# BEP31_final_stencil.net
KiCad netlist of a schematic drawn in EAGLE
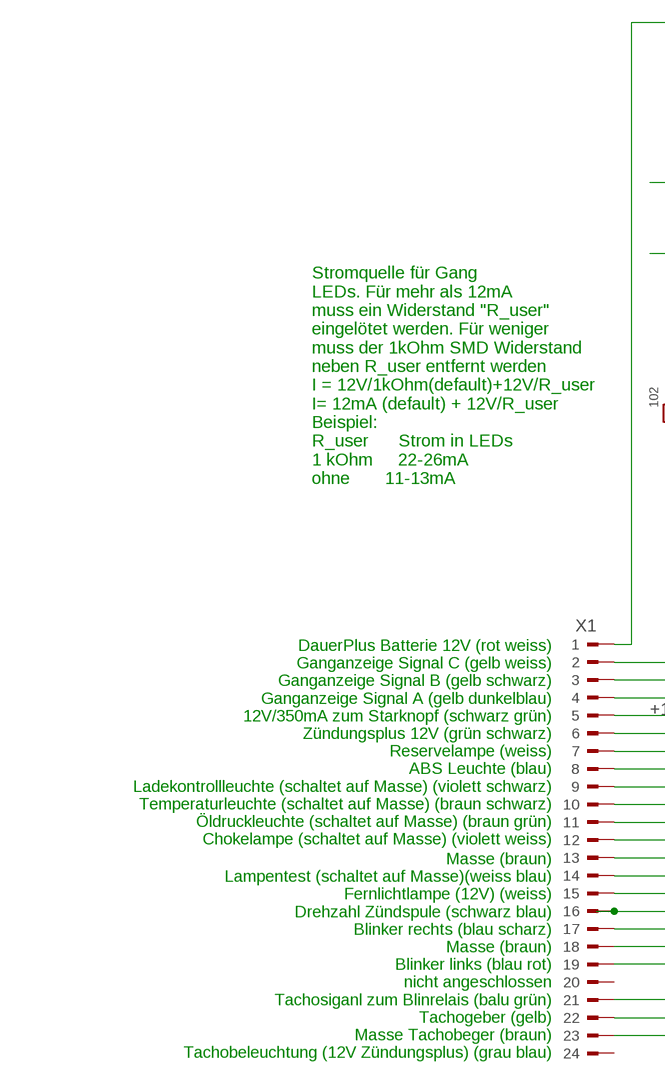
[diagram p0: schematic, sheet 1, part 1 of 2]
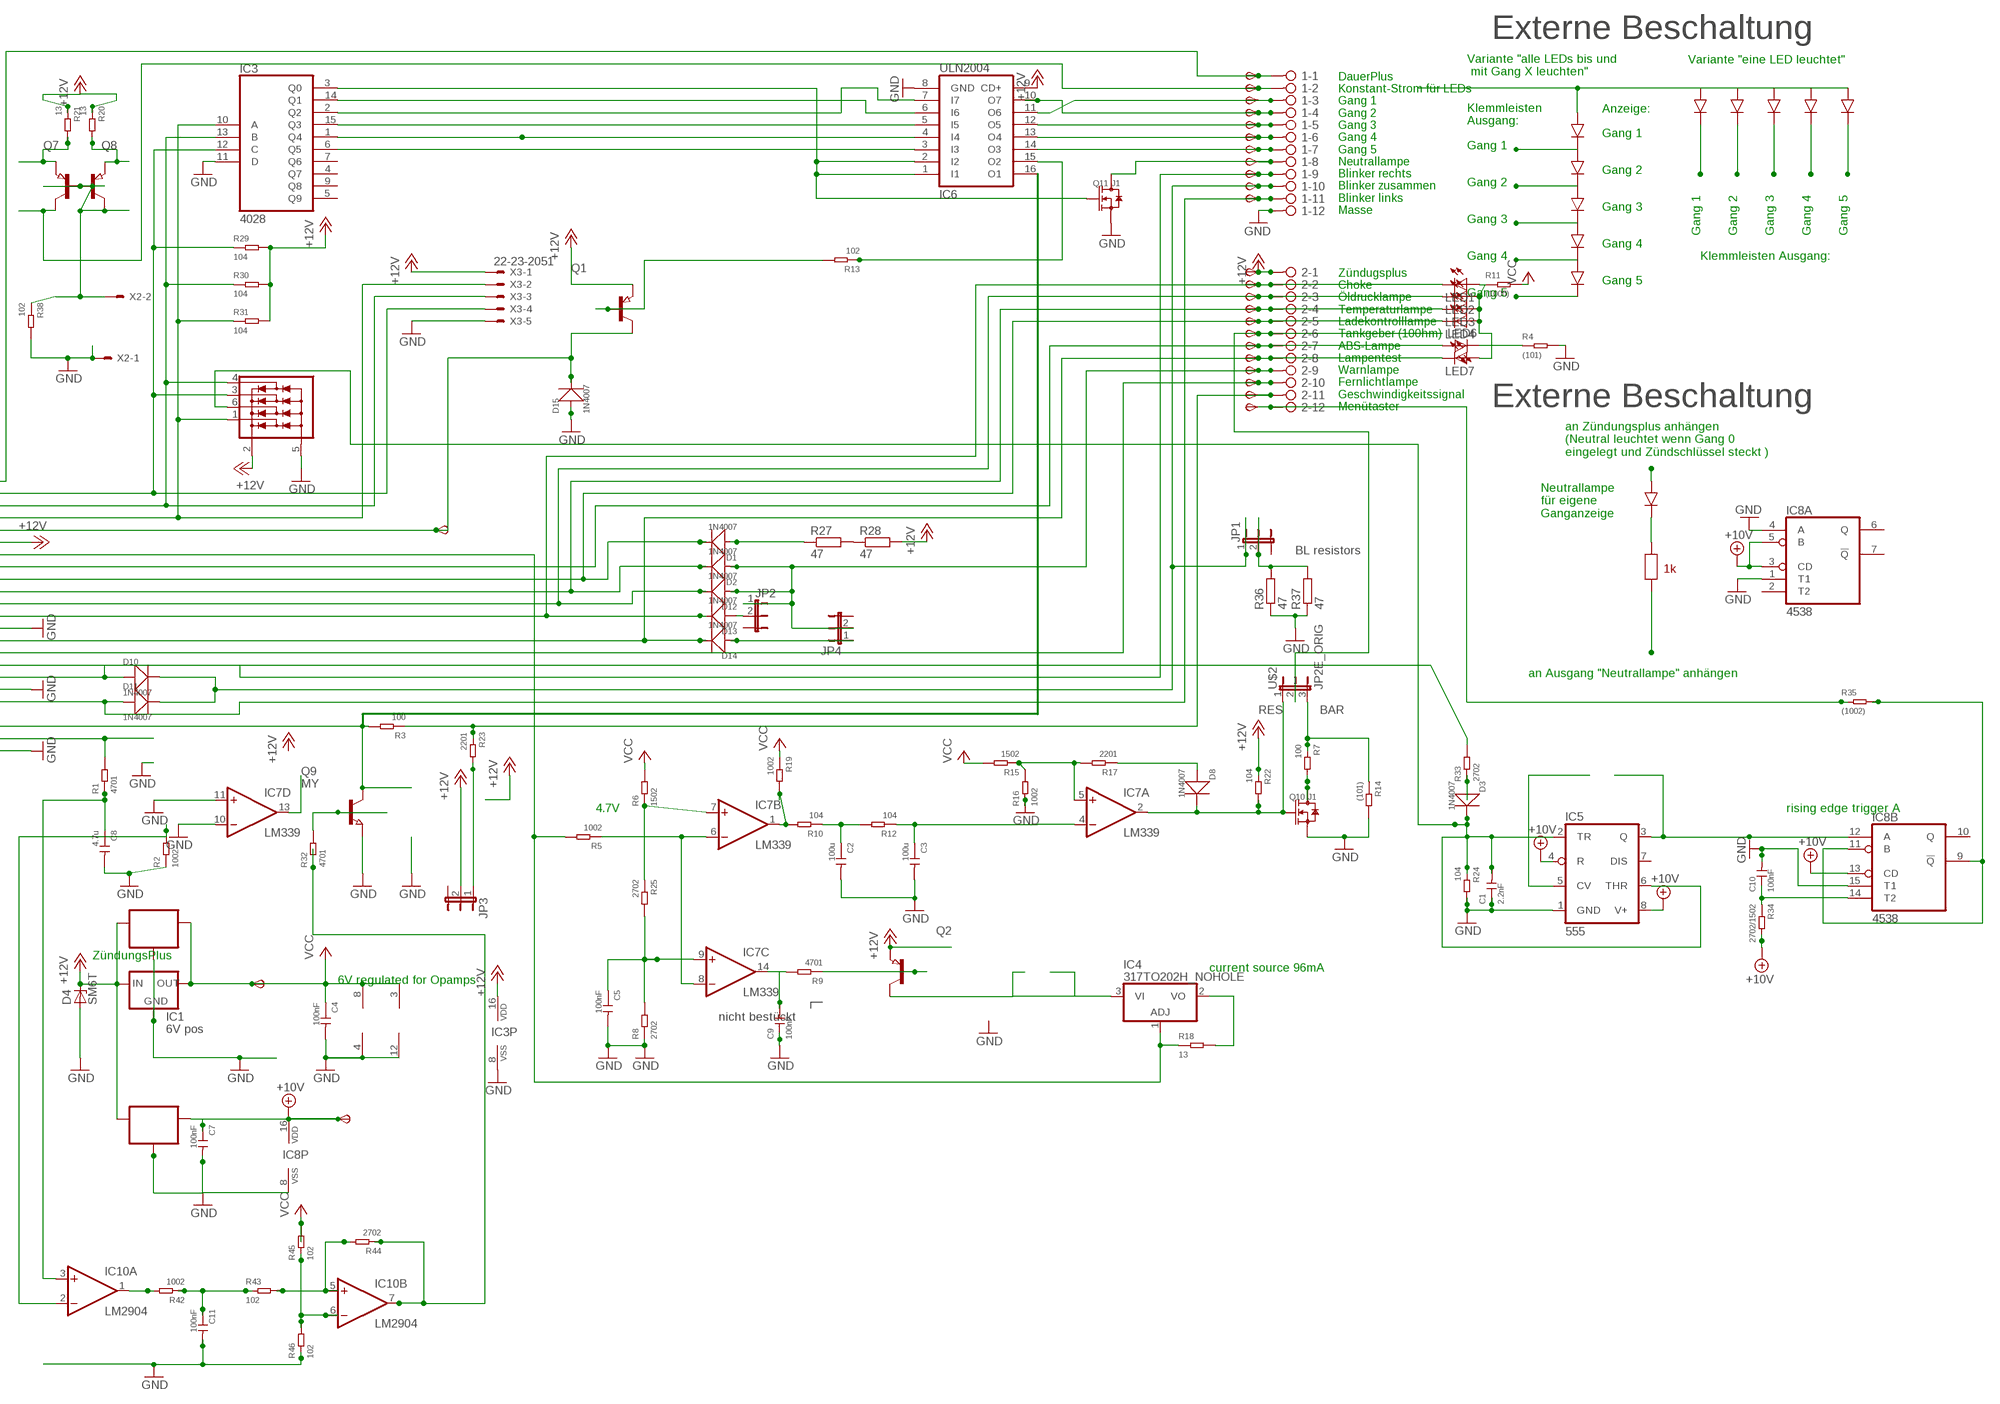
[diagram p1: schematic, sheet 1, part 2 of 2]

(export (version "E")
  (design (tool "Eeschema 10.0.6"))
  (components
    (comp (ref "1")
      (value "2081-1132")
      (footprint "eagle-import:12-PIN")
      (libsource (lib "eagle-import") (part "2081-1132"))
    )
    (comp (ref "2")
      (value "2081-1132")
      (footprint "eagle-import:12-PIN")
      (libsource (lib "eagle-import") (part "2081-1132"))
    )
    (comp (ref "6V")
      (value "TPSB2.0")
      (footprint "eagle-import:B2.0")
      (libsource (lib "eagle-import") (part "TPSB2.0"))
    )
    (comp (ref "10V")
      (value "TPSB2.0")
      (footprint "eagle-import:B2.0")
      (libsource (lib "eagle-import") (part "TPSB2.0"))
    )
    (comp (ref "C1")
      (value "2.2nF")
      (footprint "eagle-import:C0805")
      (fields (field (name "MPN") "CC0805KRX7R9BB104"))
      (libsource (lib "eagle-import") (part "CERAMIC-100NF-50V-10%-X7R(0805)"))
    )
    (comp (ref "C2")
      (value "100u")
      (footprint "eagle-import:C1206")
      (fields (field (name "MPN") "GRM31CR60J107ME39L"))
      (libsource (lib "eagle-import") (part "CERAMIC-100UF-6.3V-20%-X5R(1206)"))
    )
    (comp (ref "C3")
      (value "100u")
      (footprint "eagle-import:C1206")
      (fields (field (name "MPN") "GRM31CR60J107ME39L"))
      (libsource (lib "eagle-import") (part "CERAMIC-100UF-6.3V-20%-X5R(1206)"))
    )
    (comp (ref "C4")
      (value "100nF")
      (footprint "eagle-import:C0805")
      (fields (field (name "MPN") "CC0805KRX7R9BB104"))
      (libsource (lib "eagle-import") (part "CERAMIC-100NF-50V-10%-X7R(0805)"))
    )
    (comp (ref "C5")
      (value "100nF")
      (footprint "eagle-import:C0805")
      (fields (field (name "MPN") "CC0805KRX7R9BB104"))
      (libsource (lib "eagle-import") (part "CERAMIC-100NF-50V-10%-X7R(0805)"))
    )
    (comp (ref "C7")
      (value "100nF")
      (footprint "eagle-import:C0805")
      (fields (field (name "MPN") "CC0805KRX7R9BB104"))
      (libsource (lib "eagle-import") (part "CERAMIC-100NF-50V-10%-X7R(0805)"))
    )
    (comp (ref "C8")
      (value "4.7u")
      (footprint "eagle-import:C0805")
      (fields (field (name "MPN") "CC0805KKX5R8BB475"))
      (libsource (lib "eagle-import") (part "CERAMIC-4.7UF-25V-10%-X5R(0805)"))
    )
    (comp (ref "C9")
      (value "100nF")
      (footprint "eagle-import:C0805")
      (fields (field (name "MPN") "CC0805KRX7R9BB104"))
      (libsource (lib "eagle-import") (part "CERAMIC-100NF-50V-10%-X7R(0805)"))
    )
    (comp (ref "C10")
      (value "100nF")
      (footprint "eagle-import:C0805")
      (fields (field (name "MPN") "CC0805KRX7R9BB104"))
      (libsource (lib "eagle-import") (part "CERAMIC-100NF-50V-10%-X7R(0805)"))
    )
    (comp (ref "C11")
      (value "100nF")
      (footprint "eagle-import:C0805")
      (fields (field (name "MPN") "CC0805KRX7R9BB104"))
      (libsource (lib "eagle-import") (part "CERAMIC-100NF-50V-10%-X7R(0805)"))
    )
    (comp (ref "D1")
      (value "1N4007")
      (footprint "eagle-import:DO-214AC")
      (libsource (lib "eagle-import") (part "DIODE-GEN-PURPOSE-1KV-1A(DO-214AC)"))
    )
    (comp (ref "D2")
      (value "1N4007")
      (footprint "eagle-import:DO-214AC-1206MOUNT")
      (libsource (lib "eagle-import") (part "DIODE-GEN-PURPOSE-1KV-1A(DO-214AC)DO-214AC/1206"))
    )
    (comp (ref "D3")
      (value "1N4007")
      (footprint "eagle-import:DO-214AC")
      (libsource (lib "eagle-import") (part "DIODE-GEN-PURPOSE-1KV-1A(DO-214AC)"))
    )
    (comp (ref "D4")
      (value "SM6T")
      (footprint "eagle-import:DO214AA")
      (libsource (lib "eagle-import") (part "SM6T"))
    )
    (comp (ref "D8")
      (value "1N4007")
      (footprint "eagle-import:DO-214AC")
      (libsource (lib "eagle-import") (part "DIODE-GEN-PURPOSE-1KV-1A(DO-214AC)"))
    )
    (comp (ref "D10")
      (value "1N4007")
      (footprint "eagle-import:DO-214AC")
      (libsource (lib "eagle-import") (part "DIODE-GEN-PURPOSE-1KV-1A(DO-214AC)"))
    )
    (comp (ref "D11")
      (value "1N4007")
      (footprint "eagle-import:DO-214AC")
      (libsource (lib "eagle-import") (part "DIODE-GEN-PURPOSE-1KV-1A(DO-214AC)"))
    )
    (comp (ref "D12")
      (value "1N4007")
      (footprint "eagle-import:DO-214AC-1206MOUNT")
      (libsource (lib "eagle-import") (part "DIODE-GEN-PURPOSE-1KV-1A(DO-214AC)DO-214AC/1206"))
    )
    (comp (ref "D13")
      (value "1N4007")
      (footprint "eagle-import:DO-214AC-1206MOUNT")
      (libsource (lib "eagle-import") (part "DIODE-GEN-PURPOSE-1KV-1A(DO-214AC)DO-214AC/1206"))
    )
    (comp (ref "D14")
      (value "1N4007")
      (footprint "eagle-import:DO-214AC-1206MOUNT")
      (libsource (lib "eagle-import") (part "DIODE-GEN-PURPOSE-1KV-1A(DO-214AC)DO-214AC/1206"))
    )
    (comp (ref "D15")
      (value "1N4007")
      (footprint "eagle-import:DO-214AC")
      (libsource (lib "eagle-import") (part "DIODE-GEN-PURPOSE-1KV-1A(DO-214AC)"))
    )
    (comp (ref "IC1")
      (value "6V pos")
      (footprint "eagle-import:78LXX")
      (libsource (lib "eagle-import") (part "v-reg_78LXX"))
    )
    (comp (ref "IC2")
      (value "78LXXSOT89_ROUND")
      (footprint "eagle-import:SOT89_ROUND")
      (libsource (lib "eagle-import") (part "78LXXSOT89_ROUND"))
    )
    (comp (ref "IC3")
      (value "4028")
      (footprint "eagle-import:SO16")
      (libsource (lib "eagle-import") (part "4028D"))
    )
    (comp (ref "IC4")
      (value "317TO202H_NOHOLE")
      (footprint "eagle-import:TO220H_NOHOLE")
      (libsource (lib "eagle-import") (part "317TO202H_NOHOLE"))
    )
    (comp (ref "IC5")
      (value "555")
      (footprint "eagle-import:SO08")
      (libsource (lib "eagle-import") (part "555DNE"))
    )
    (comp (ref "IC6")
      (value "ULN2004")
      (footprint "eagle-import:SO16")
      (libsource (lib "eagle-import") (part "ULN2004AD"))
    )
    (comp (ref "IC7")
      (value "LM339")
      (footprint "eagle-import:SO14")
      (libsource (lib "eagle-import") (part "LM339D"))
    )
    (comp (ref "IC8")
      (value "4538")
      (footprint "eagle-import:SO16")
      (libsource (lib "eagle-import") (part "4538D"))
    )
    (comp (ref "IC9")
      (value "78LXXSOT89_ROUND")
      (footprint "eagle-import:SOT89_ROUND")
      (libsource (lib "eagle-import") (part "78LXXSOT89_ROUND"))
    )
    (comp (ref "IC10")
      (value "LM2904")
      (footprint "eagle-import:SO08")
      (libsource (lib "eagle-import") (part "LM358D"))
    )
    (comp (ref "JP1")
      (value "JP2EJP2_SMALLPADS")
      (footprint "eagle-import:JP2_SMALLPADS")
      (libsource (lib "eagle-import") (part "JP2EJP2_SMALLPADS"))
    )
    (comp (ref "JP2")
      (value "JP2EJP2_SMALLPADS")
      (footprint "eagle-import:JP2_SMALLPADS")
      (libsource (lib "eagle-import") (part "JP2EJP2_SMALLPADS"))
    )
    (comp (ref "JP3")
      (value "JP2EJP2_SMALLPADS")
      (footprint "eagle-import:JP2_SMALLPADS")
      (libsource (lib "eagle-import") (part "JP2EJP2_SMALLPADS"))
    )
    (comp (ref "JP4")
      (value "JP2EJP2_SMALLPADS")
      (footprint "eagle-import:JP2_SMALLPADS")
      (libsource (lib "eagle-import") (part "JP2EJP2_SMALLPADS"))
    )
    (comp (ref "LED1")
      (value "LEDLD260")
      (footprint "eagle-import:LD260")
      (libsource (lib "eagle-import") (part "LEDLD260"))
    )
    (comp (ref "LED2")
      (value "LEDLD260")
      (footprint "eagle-import:LD260")
      (libsource (lib "eagle-import") (part "LEDLD260"))
    )
    (comp (ref "LED3")
      (value "LEDLD260")
      (footprint "eagle-import:LD260")
      (libsource (lib "eagle-import") (part "LEDLD260"))
    )
    (comp (ref "LED4")
      (value "LEDLD260")
      (footprint "eagle-import:LD260")
      (libsource (lib "eagle-import") (part "LEDLD260"))
    )
    (comp (ref "LED6")
      (value "LEDLD260")
      (footprint "eagle-import:LD260")
      (libsource (lib "eagle-import") (part "LEDLD260"))
    )
    (comp (ref "LED7")
      (value "LEDLD260")
      (footprint "eagle-import:LD260")
      (libsource (lib "eagle-import") (part "LEDLD260"))
    )
    (comp (ref "Q1")
      (value "PNP-TRANSISTOR_SOT89")
      (footprint "eagle-import:SOT89")
      (libsource (lib "eagle-import") (part "PNP-TRANSISTOR_SOT89"))
    )
    (comp (ref "Q2")
      (value "PNP-TRANSISTOR_SOT89")
      (footprint "eagle-import:SOT89")
      (libsource (lib "eagle-import") (part "PNP-TRANSISTOR_SOT89"))
    )
    (comp (ref "Q7")
      (value "PNP-TRANSISTOR_SOT89")
      (footprint "eagle-import:SOT89")
      (libsource (lib "eagle-import") (part "PNP-TRANSISTOR_SOT89"))
    )
    (comp (ref "Q8")
      (value "PNP-TRANSISTOR_SOT89")
      (footprint "eagle-import:SOT89")
      (libsource (lib "eagle-import") (part "PNP-TRANSISTOR_SOT89"))
    )
    (comp (ref "Q9")
      (value "MY")
      (footprint "eagle-import:SOT89")
      (libsource (lib "eagle-import") (part "NPN-TRANSISTOR_SOT89"))
    )
    (comp (ref "Q10")
      (value "J1")
      (footprint "eagle-import:SOT-23")
      (fields (field (name "MPN") "BSS138W-7-F"))
      (libsource (lib "eagle-import") (part "SMD-MOSFET-N-CH-50V-200MA-BSS138W-7-F(SOT-23)"))
    )
    (comp (ref "Q11")
      (value "J1")
      (footprint "eagle-import:SOT-23")
      (fields (field (name "MPN") "BSS138W-7-F"))
      (libsource (lib "eagle-import") (part "SMD-MOSFET-N-CH-50V-200MA-BSS138W-7-F(SOT-23)"))
    )
    (comp (ref "R1")
      (value "4701")
      (footprint "eagle-import:R0805")
      (fields (field (name "MPN") "RC0805JR-074K7L"))
      (libsource (lib "eagle-import") (part "SMD-RES-4.7K-5%-1/8W(0805)"))
    )
    (comp (ref "R2")
      (value "1002")
      (footprint "eagle-import:R0805")
      (fields (field (name "MPN") "RC0805FR-0710KL"))
      (libsource (lib "eagle-import") (part "SMD-RES-10K-1%-1/8W(0805)"))
    )
    (comp (ref "R3")
      (value "100")
      (footprint "eagle-import:R0805")
      (fields (field (name "MPN") "RC0805JR-07220RL"))
      (libsource (lib "eagle-import") (part "SMD-RES-220R-5%-1/8W(0805)"))
    )
    (comp (ref "R4")
      (value "(101)")
      (footprint "eagle-import:R0805")
      (fields (field (name "MPN") "RC0805JR-07100RL"))
      (libsource (lib "eagle-import") (part "SMD-RES-100R-5%-1/8W(0805)"))
    )
    (comp (ref "R5")
      (value "1002")
      (footprint "eagle-import:R0805")
      (fields (field (name "MPN") "RC0805FR-0710KL"))
      (libsource (lib "eagle-import") (part "SMD-RES-10K-1%-1/8W(0805)"))
    )
    (comp (ref "R6")
      (value "1502")
      (footprint "eagle-import:R0805")
      (fields (field (name "MPN") "RC0805FR-0710KL"))
      (libsource (lib "eagle-import") (part "SMD-RES-10K-1%-1/8W(0805)"))
    )
    (comp (ref "R7")
      (value "100")
      (footprint "eagle-import:R0805")
      (fields (field (name "MPN") "RC0805JR-072K2L"))
      (libsource (lib "eagle-import") (part "SMD-RES-2.2K-5%-1/8W(0805)"))
    )
    (comp (ref "R8")
      (value "2702")
      (footprint "eagle-import:R0805")
      (fields (field (name "MPN") "RC0805JR-074K7L"))
      (libsource (lib "eagle-import") (part "SMD-RES-4.7K-5%-1/8W(0805)"))
    )
    (comp (ref "R9")
      (value "4701")
      (footprint "eagle-import:R0805")
      (fields (field (name "MPN") "RC0805JR-074K7L"))
      (libsource (lib "eagle-import") (part "SMD-RES-4.7K-5%-1/8W(0805)"))
    )
    (comp (ref "R10")
      (value "104")
      (footprint "eagle-import:R0805")
      (fields (field (name "MPN") "RC0805FR-0710KL"))
      (libsource (lib "eagle-import") (part "SMD-RES-10K-1%-1/8W(0805)"))
    )
    (comp (ref "R11")
      (value "(1000)")
      (footprint "eagle-import:R0805")
      (fields (field (name "MPN") "RC0805JR-07100RL"))
      (libsource (lib "eagle-import") (part "SMD-RES-100R-5%-1/8W(0805)"))
    )
    (comp (ref "R12")
      (value "104")
      (footprint "eagle-import:R0805")
      (fields (field (name "MPN") "RC0805FR-0710KL"))
      (libsource (lib "eagle-import") (part "SMD-RES-10K-1%-1/8W(0805)"))
    )
    (comp (ref "R13")
      (value "102")
      (footprint "eagle-import:R0805")
      (fields (field (name "MPN") "RC0805JR-071KL"))
      (libsource (lib "eagle-import") (part "SMD-RES-1K-5%-1/8W(0805)"))
    )
    (comp (ref "R14")
      (value "(101)")
      (footprint "eagle-import:R0805")
      (fields (field (name "MPN") "RC0805JR-072K2L"))
      (libsource (lib "eagle-import") (part "SMD-RES-2.2K-5%-1/8W(0805)"))
    )
    (comp (ref "R15")
      (value "1502")
      (footprint "eagle-import:R0805")
      (fields (field (name "MPN") "RC0805FR-0710KL"))
      (libsource (lib "eagle-import") (part "SMD-RES-10K-1%-1/8W(0805)"))
    )
    (comp (ref "R16")
      (value "1002")
      (footprint "eagle-import:R0805")
      (fields (field (name "MPN") "RC0805FR-0710KL"))
      (libsource (lib "eagle-import") (part "SMD-RES-10K-1%-1/8W(0805)"))
    )
    (comp (ref "R17")
      (value "2201")
      (footprint "eagle-import:R0805")
      (fields (field (name "MPN") "RC0805JR-072K2L"))
      (libsource (lib "eagle-import") (part "SMD-RES-2.2K-5%-1/8W(0805)"))
    )
    (comp (ref "R18")
      (value "13")
      (footprint "eagle-import:R1206")
      (fields (field (name "MPN") "RC1206JR-0713RL"))
      (libsource (lib "eagle-import") (part "SMD-RES-13R-5%-1/4W(1206)"))
    )
    (comp (ref "R19")
      (value "1002")
      (footprint "eagle-import:R0805")
      (fields (field (name "MPN") "RC0805FR-0710KL"))
      (libsource (lib "eagle-import") (part "SMD-RES-10K-1%-1/8W(0805)"))
    )
    (comp (ref "R20")
      (value "13")
      (footprint "eagle-import:R1206")
      (fields (field (name "MPN") "RC1206JR-0713RL"))
      (libsource (lib "eagle-import") (part "SMD-RES-13R-5%-1/4W(1206)"))
    )
    (comp (ref "R21")
      (value "13")
      (footprint "eagle-import:R1206")
      (fields (field (name "MPN") "RC1206JR-0713RL"))
      (libsource (lib "eagle-import") (part "SMD-RES-13R-5%-1/4W(1206)"))
    )
    (comp (ref "R22")
      (value "104")
      (footprint "eagle-import:R0805")
      (fields (field (name "MPN") "RC0805FR-0710KL"))
      (libsource (lib "eagle-import") (part "SMD-RES-10K-1%-1/8W(0805)"))
    )
    (comp (ref "R23")
      (value "2201")
      (footprint "eagle-import:R0805")
      (fields (field (name "MPN") "RC0805JR-072K2L"))
      (libsource (lib "eagle-import") (part "SMD-RES-2.2K-5%-1/8W(0805)"))
    )
    (comp (ref "R24")
      (value "104")
      (footprint "eagle-import:R0805")
      (fields (field (name "MPN") "RC0805FR-0710KL"))
      (libsource (lib "eagle-import") (part "SMD-RES-10K-1%-1/8W(0805)"))
    )
    (comp (ref "R25")
      (value "2702")
      (footprint "eagle-import:R0805")
      (fields (field (name "MPN") "RC0805JR-074K7L"))
      (libsource (lib "eagle-import") (part "SMD-RES-4.7K-5%-1/8W(0805)"))
    )
    (comp (ref "R27")
      (value "47")
      (footprint "eagle-import:V235_17_1MM")
      (libsource (lib "eagle-import") (part "R-EU_V235/17_1MM"))
    )
    (comp (ref "R28")
      (value "47")
      (footprint "eagle-import:V235_17_1MM")
      (libsource (lib "eagle-import") (part "R-EU_V235/17_1MM"))
    )
    (comp (ref "R29")
      (value "104")
      (footprint "eagle-import:R0805")
      (fields (field (name "MPN") "RC0805FR-0710KL"))
      (libsource (lib "eagle-import") (part "SMD-RES-10K-1%-1/8W(0805)"))
    )
    (comp (ref "R30")
      (value "104")
      (footprint "eagle-import:R0805")
      (fields (field (name "MPN") "RC0805FR-0710KL"))
      (libsource (lib "eagle-import") (part "SMD-RES-10K-1%-1/8W(0805)"))
    )
    (comp (ref "R31")
      (value "104")
      (footprint "eagle-import:R0805")
      (fields (field (name "MPN") "RC0805FR-0710KL"))
      (libsource (lib "eagle-import") (part "SMD-RES-10K-1%-1/8W(0805)"))
    )
    (comp (ref "R32")
      (value "4701")
      (footprint "eagle-import:R0805")
      (fields (field (name "MPN") "RC0805JR-074K7L"))
      (libsource (lib "eagle-import") (part "SMD-RES-4.7K-5%-1/8W(0805)"))
    )
    (comp (ref "R33")
      (value "2702")
      (footprint "eagle-import:R0805")
      (fields (field (name "MPN") "RC0805FR-0710KL"))
      (libsource (lib "eagle-import") (part "SMD-RES-10K-1%-1/8W(0805)"))
    )
    (comp (ref "R34")
      (value "2702/1502")
      (footprint "eagle-import:R0805")
      (fields (field (name "MPN") "RC0805JR-074K7L"))
      (libsource (lib "eagle-import") (part "SMD-RES-4.7K-5%-1/8W(0805)"))
    )
    (comp (ref "R35")
      (value "(1002)")
      (footprint "eagle-import:R0805")
      (fields (field (name "MPN") "RC0805JR-074K7L"))
      (libsource (lib "eagle-import") (part "SMD-RES-4.7K-5%-1/8W(0805)"))
    )
    (comp (ref "R36")
      (value "47")
      (footprint "eagle-import:V235_17_1MM")
      (libsource (lib "eagle-import") (part "R-EU_V235/17_1MM"))
    )
    (comp (ref "R37")
      (value "47")
      (footprint "eagle-import:V235_17_1MM")
      (libsource (lib "eagle-import") (part "R-EU_V235/17_1MM"))
    )
    (comp (ref "R38")
      (value "102")
      (footprint "eagle-import:R0805")
      (fields (field (name "MPN") "RC0805JR-071KL"))
      (libsource (lib "eagle-import") (part "SMD-RES-1K-5%-1/8W(0805)"))
    )
    (comp (ref "R42")
      (value "1002")
      (footprint "eagle-import:R0805")
      (fields (field (name "MPN") "RC0805FR-0710KL"))
      (libsource (lib "eagle-import") (part "SMD-RES-10K-1%-1/8W(0805)"))
    )
    (comp (ref "R43")
      (value "102")
      (footprint "eagle-import:R0805")
      (fields (field (name "MPN") "RC0805JR-071KL"))
      (libsource (lib "eagle-import") (part "SMD-RES-1K-5%-1/8W(0805)"))
    )
    (comp (ref "R44")
      (value "2702")
      (footprint "eagle-import:R0805")
      (fields (field (name "MPN") "RC0805JR-074K7L"))
      (libsource (lib "eagle-import") (part "SMD-RES-4.7K-5%-1/8W(0805)"))
    )
    (comp (ref "R45")
      (value "102")
      (footprint "eagle-import:R0805")
      (fields (field (name "MPN") "RC0805JR-071KL"))
      (libsource (lib "eagle-import") (part "SMD-RES-1K-5%-1/8W(0805)"))
    )
    (comp (ref "R46")
      (value "102")
      (footprint "eagle-import:R0805")
      (fields (field (name "MPN") "RC0805JR-071KL"))
      (libsource (lib "eagle-import") (part "SMD-RES-1K-5%-1/8W(0805)"))
    )
    (comp (ref "START")
      (value "TPSB2.0")
      (footprint "eagle-import:B2.0")
      (libsource (lib "eagle-import") (part "TPSB2.0"))
    )
    (comp (ref "TP1")
      (value "TPSB2.0")
      (footprint "eagle-import:B2.0")
      (libsource (lib "eagle-import") (part "TPSB2.0"))
    )
    (comp (ref "TP2")
      (value "TPSB2.0")
      (footprint "eagle-import:B2.0")
      (libsource (lib "eagle-import") (part "TPSB2.0"))
    )
    (comp (ref "TP3")
      (value "TPSB2.0")
      (footprint "eagle-import:B2.0")
      (libsource (lib "eagle-import") (part "TPSB2.0"))
    )
    (comp (ref "TP4")
      (value "TPSB2.0")
      (footprint "eagle-import:B2.0")
      (libsource (lib "eagle-import") (part "TPSB2.0"))
    )
    (comp (ref "TP5")
      (value "TPSB2.0")
      (footprint "eagle-import:B2.0")
      (libsource (lib "eagle-import") (part "TPSB2.0"))
    )
    (comp (ref "TP6")
      (value "TPSB2.0")
      (footprint "eagle-import:B2.0")
      (libsource (lib "eagle-import") (part "TPSB2.0"))
    )
    (comp (ref "TP7")
      (value "TPSB2.0")
      (footprint "eagle-import:B2.0")
      (libsource (lib "eagle-import") (part "TPSB2.0"))
    )
    (comp (ref "TP8")
      (value "TPSB2.0")
      (footprint "eagle-import:B2.0")
      (libsource (lib "eagle-import") (part "TPSB2.0"))
    )
    (comp (ref "TP9")
      (value "TPSB2.0")
      (footprint "eagle-import:B2.0")
      (libsource (lib "eagle-import") (part "TPSB2.0"))
    )
    (comp (ref "TP10")
      (value "TPSB2.0")
      (footprint "eagle-import:B2.0")
      (libsource (lib "eagle-import") (part "TPSB2.0"))
    )
    (comp (ref "TP11")
      (value "TPSB2.0")
      (footprint "eagle-import:B2.0")
      (libsource (lib "eagle-import") (part "TPSB2.0"))
    )
    (comp (ref "TP12")
      (value "TPSB2.0")
      (footprint "eagle-import:B2.0")
      (libsource (lib "eagle-import") (part "TPSB2.0"))
    )
    (comp (ref "TP13")
      (value "TPSB2.0")
      (footprint "eagle-import:B2.0")
      (libsource (lib "eagle-import") (part "TPSB2.0"))
    )
    (comp (ref "TP16")
      (value "TPSB2.0")
      (footprint "eagle-import:B2.0")
      (libsource (lib "eagle-import") (part "TPSB2.0"))
    )
    (comp (ref "TP17")
      (value "TPSB2.0")
      (footprint "eagle-import:B2.0")
      (libsource (lib "eagle-import") (part "TPSB2.0"))
    )
    (comp (ref "TP18")
      (value "TPSB2.0")
      (footprint "eagle-import:B2.0")
      (libsource (lib "eagle-import") (part "TPSB2.0"))
    )
    (comp (ref "TP19")
      (value "TPSB2.0")
      (footprint "eagle-import:B2.0")
      (libsource (lib "eagle-import") (part "TPSB2.0"))
    )
    (comp (ref "TP21")
      (value "TPSB2.0")
      (footprint "eagle-import:B2.0")
      (libsource (lib "eagle-import") (part "TPSB2.0"))
    )
    (comp (ref "TP22")
      (value "TPSB2.0")
      (footprint "eagle-import:B2.0")
      (libsource (lib "eagle-import") (part "TPSB2.0"))
    )
    (comp (ref "TP23")
      (value "TPSB2.0")
      (footprint "eagle-import:B2.0")
      (libsource (lib "eagle-import") (part "TPSB2.0"))
    )
    (comp (ref "TP24")
      (value "TPSB1,27")
      (footprint "eagle-import:B1,27")
      (libsource (lib "eagle-import") (part "TPSB1,27"))
    )
    (comp (ref "TP25")
      (value "TPSB2.0")
      (footprint "eagle-import:B2.0")
      (libsource (lib "eagle-import") (part "TPSB2.0"))
    )
    (comp (ref "TP26")
      (value "TPSB2.0")
      (footprint "eagle-import:B2.0")
      (libsource (lib "eagle-import") (part "TPSB2.0"))
    )
    (comp (ref "U$2")
      (value "JP2E_ORIG")
      (footprint "eagle-import:JP2_ORIG_SMALLPADS")
      (libsource (lib "eagle-import") (part "JP2E_ORIG"))
    )
    (comp (ref "U$3")
      (value "NUP4304SOT457_R")
      (footprint "eagle-import:SOT457R_PHILIPS")
      (libsource (lib "eagle-import") (part "NUP4304SOT457_R"))
    )
    (comp (ref "X1")
      (value "CON_BMWV2")
      (footprint "eagle-import:24-PIN_V2")
      (libsource (lib "eagle-import") (part "CON_BMWV2"))
    )
    (comp (ref "X2")
      (value "22-23-2021")
      (footprint "eagle-import:22-23-2021")
      (fields (field (name "MF") "MOLEX"))
      (libsource (lib "eagle-import") (part "22-23-2021"))
    )
    (comp (ref "X3")
      (value "22-23-2051")
      (footprint "eagle-import:22-23-2051")
      (fields (field (name "MF") "MOLEX"))
      (libsource (lib "eagle-import") (part "22-23-2051"))
    )
  )
  (nets
    (net (code "1") (name "+10V") (class "Default")
      (node (ref "10V") (pin "TP") (pinfunction "PP_TP") (pintype "input"))
      (node (ref "C7") (pin "1") (pinfunction "1_1") (pintype "passive"))
      (node (ref "IC5") (pin "4") (pinfunction "R_4") (pintype "input"))
      (node (ref "IC5") (pin "8") (pinfunction "V+_8") (pintype "power_in"))
      (node (ref "IC8") (pin "13") (pinfunction "CD_13") (pintype "input"))
      (node (ref "IC8") (pin "16") (pinfunction "VDD_16") (pintype "power_in"))
      (node (ref "IC8") (pin "3") (pinfunction "CD_3") (pintype "input"))
      (node (ref "IC8") (pin "5") (pinfunction "B_5") (pintype "input"))
      (node (ref "IC9") (pin "1") (pinfunction "OUT_1") (pintype "passive"))
      (node (ref "R34") (pin "2") (pinfunction "2_2") (pintype "passive"))
    )
    (net (code "2") (name "+12V") (class "Default")
      (node (ref "2") (pin "1") (pinfunction "KL_1") (pintype "passive"))
      (node (ref "D4") (pin "C") (pinfunction "C_C") (pintype "passive"))
      (node (ref "IC1") (pin "IN") (pinfunction "IN_IN") (pintype "input"))
      (node (ref "IC2") (pin "3") (pinfunction "IN_3") (pintype "input"))
      (node (ref "IC3") (pin "16") (pinfunction "VDD_16") (pintype "power_in"))
      (node (ref "IC6") (pin "9") (pinfunction "CD+_9") (pintype "passive"))
      (node (ref "IC9") (pin "3") (pinfunction "IN_3") (pintype "input"))
      (node (ref "JP3") (pin "2") (pinfunction "2_2") (pintype "passive"))
      (node (ref "Q1") (pin "3") (pinfunction "E_3") (pintype "passive"))
      (node (ref "Q2") (pin "3") (pinfunction "E_3") (pintype "passive"))
      (node (ref "R20") (pin "1") (pinfunction "1_1") (pintype "passive"))
      (node (ref "R21") (pin "1") (pinfunction "1_1") (pintype "passive"))
      (node (ref "R22") (pin "1") (pinfunction "1_1") (pintype "passive"))
      (node (ref "R28") (pin "2") (pinfunction "2_2") (pintype "passive"))
      (node (ref "R29") (pin "2") (pinfunction "2_2") (pintype "passive"))
      (node (ref "R30") (pin "2") (pinfunction "2_2") (pintype "passive"))
      (node (ref "R31") (pin "2") (pinfunction "2_2") (pintype "passive"))
      (node (ref "TP12") (pin "TP") (pinfunction "PP_TP") (pintype "input"))
      (node (ref "U$3") (pin "2") (pinfunction "V+_2") (pintype "passive"))
      (node (ref "X1") (pin "6") (pinfunction "6_6") (pintype "passive"))
      (node (ref "X3") (pin "1") (pinfunction "S_1") (pintype "passive"))
    )
    (net (code "3") (name "GND") (class "Default")
      (node (ref "1") (pin "12") (pinfunction "KL_12") (pintype "passive"))
      (node (ref "C1") (pin "1") (pinfunction "1_1") (pintype "passive"))
      (node (ref "C10") (pin "2") (pinfunction "2_2") (pintype "passive"))
      (node (ref "C11") (pin "2") (pinfunction "2_2") (pintype "passive"))
      (node (ref "C2") (pin "2") (pinfunction "2_2") (pintype "passive"))
      (node (ref "C3") (pin "2") (pinfunction "2_2") (pintype "passive"))
      (node (ref "C4") (pin "2") (pinfunction "2_2") (pintype "passive"))
      (node (ref "C5") (pin "2") (pinfunction "2_2") (pintype "passive"))
      (node (ref "C7") (pin "2") (pinfunction "2_2") (pintype "passive"))
      (node (ref "C8") (pin "2") (pinfunction "2_2") (pintype "passive"))
      (node (ref "C9") (pin "1") (pinfunction "1_1") (pintype "passive"))
      (node (ref "D15") (pin "1") (pinfunction "+_1") (pintype "passive"))
      (node (ref "D4") (pin "A") (pinfunction "A_A") (pintype "passive"))
      (node (ref "IC1") (pin "GND") (pinfunction "GND_GND") (pintype "input"))
      (node (ref "IC10") (pin "4") (pinfunction "V-_4") (pintype "power_in"))
      (node (ref "IC2") (pin "2") (pinfunction "GND_2") (pintype "input"))
      (node (ref "IC2") (pin "2@1") (pinfunction "GND_2@1") (pintype "input"))
      (node (ref "IC3") (pin "11") (pinfunction "D_11") (pintype "input"))
      (node (ref "IC3") (pin "8") (pinfunction "VSS_8") (pintype "power_in"))
      (node (ref "IC5") (pin "1") (pinfunction "GND_1") (pintype "power_in"))
      (node (ref "IC6") (pin "8") (pinfunction "GND_8") (pintype "power_in"))
      (node (ref "IC7") (pin "10") (pinfunction "-IN_10") (pintype "input"))
      (node (ref "IC7") (pin "11") (pinfunction "+IN_11") (pintype "input"))
      (node (ref "IC7") (pin "12") (pinfunction "GND_12") (pintype "power_in"))
      (node (ref "IC8") (pin "1") (pinfunction "T1_1") (pintype "input"))
      (node (ref "IC8") (pin "15") (pinfunction "T1_15") (pintype "input"))
      (node (ref "IC8") (pin "4") (pinfunction "A_4") (pintype "input"))
      (node (ref "IC8") (pin "8") (pinfunction "VSS_8") (pintype "power_in"))
      (node (ref "IC9") (pin "2") (pinfunction "GND_2") (pintype "input"))
      (node (ref "IC9") (pin "2@1") (pinfunction "GND_2@1") (pintype "input"))
      (node (ref "Q10") (pin "2") (pinfunction "S_2") (pintype "passive"))
      (node (ref "Q11") (pin "2") (pinfunction "S_2") (pintype "passive"))
      (node (ref "Q9") (pin "3") (pinfunction "E_3") (pintype "passive"))
      (node (ref "R14") (pin "2") (pinfunction "2_2") (pintype "passive"))
      (node (ref "R16") (pin "1") (pinfunction "1_1") (pintype "passive"))
      (node (ref "R2") (pin "1") (pinfunction "1_1") (pintype "passive"))
      (node (ref "R24") (pin "2") (pinfunction "2_2") (pintype "passive"))
      (node (ref "R36") (pin "1") (pinfunction "1_1") (pintype "passive"))
      (node (ref "R37") (pin "1") (pinfunction "1_1") (pintype "passive"))
      (node (ref "R38") (pin "2") (pinfunction "2_2") (pintype "passive"))
      (node (ref "R4") (pin "2") (pinfunction "2_2") (pintype "passive"))
      (node (ref "R46") (pin "1") (pinfunction "1_1") (pintype "passive"))
      (node (ref "R8") (pin "1") (pinfunction "1_1") (pintype "passive"))
      (node (ref "U$3") (pin "5") (pinfunction "V-_5") (pintype "passive"))
      (node (ref "X1") (pin "13") (pinfunction "13_13") (pintype "passive"))
      (node (ref "X1") (pin "18") (pinfunction "18_18") (pintype "passive"))
      (node (ref "X1") (pin "23") (pinfunction "23_23") (pintype "passive"))
      (node (ref "X2") (pin "1") (pinfunction "S_1") (pintype "passive"))
      (node (ref "X3") (pin "5") (pinfunction "S_5") (pintype "passive"))
    )
    (net (code "4") (name "Net-(1A-KL)") (class "Default")
      (node (ref "1") (pin "1") (pinfunction "KL_1") (pintype "passive"))
      (node (ref "TP1") (pin "TP") (pinfunction "PP_TP") (pintype "input"))
      (node (ref "X1") (pin "1") (pinfunction "1_1") (pintype "passive"))
    )
    (net (code "5") (name "Net-(1B-KL)") (class "Default")
      (node (ref "1") (pin "10") (pinfunction "KL_10") (pintype "passive"))
      (node (ref "D10") (pin "2") (pinfunction "-_2") (pintype "passive"))
      (node (ref "D11") (pin "2") (pinfunction "-_2") (pintype "passive"))
      (node (ref "JP1") (pin "1") (pinfunction "1_1") (pintype "passive"))
      (node (ref "TP10") (pin "TP") (pinfunction "PP_TP") (pintype "input"))
    )
    (net (code "6") (name "Net-(1C-KL)") (class "Default")
      (node (ref "1") (pin "11") (pinfunction "KL_11") (pintype "passive"))
      (node (ref "D11") (pin "1") (pinfunction "+_1") (pintype "passive"))
      (node (ref "TP11") (pin "TP") (pinfunction "PP_TP") (pintype "input"))
      (node (ref "X1") (pin "19") (pinfunction "19_19") (pintype "passive"))
    )
    (net (code "7") (name "Net-(1E-KL)") (class "Default")
      (node (ref "1") (pin "2") (pinfunction "KL_2") (pintype "passive"))
      (node (ref "Q8") (pin "2") (pinfunction "C_2") (pintype "passive"))
      (node (ref "TP2") (pin "TP") (pinfunction "PP_TP") (pintype "input"))
    )
    (net (code "8") (name "Net-(1F-KL)") (class "Default")
      (node (ref "1") (pin "3") (pinfunction "KL_3") (pintype "passive"))
      (node (ref "IC6") (pin "11") (pinfunction "O6_11") (pintype "open_collector"))
      (node (ref "TP3") (pin "TP") (pinfunction "PP_TP") (pintype "input"))
    )
    (net (code "9") (name "Net-(1G-KL)") (class "Default")
      (node (ref "1") (pin "4") (pinfunction "KL_4") (pintype "passive"))
      (node (ref "IC6") (pin "10") (pinfunction "O7_10") (pintype "open_collector"))
      (node (ref "TP4") (pin "TP") (pinfunction "PP_TP") (pintype "input"))
    )
    (net (code "10") (name "Net-(1H-KL)") (class "Default")
      (node (ref "1") (pin "5") (pinfunction "KL_5") (pintype "passive"))
      (node (ref "IC6") (pin "12") (pinfunction "O5_12") (pintype "open_collector"))
      (node (ref "TP5") (pin "TP") (pinfunction "PP_TP") (pintype "input"))
    )
    (net (code "11") (name "Net-(1I-KL)") (class "Default")
      (node (ref "1") (pin "6") (pinfunction "KL_6") (pintype "passive"))
      (node (ref "IC6") (pin "13") (pinfunction "O4_13") (pintype "open_collector"))
      (node (ref "TP6") (pin "TP") (pinfunction "PP_TP") (pintype "input"))
    )
    (net (code "12") (name "Net-(1J-KL)") (class "Default")
      (node (ref "1") (pin "7") (pinfunction "KL_7") (pintype "passive"))
      (node (ref "IC6") (pin "14") (pinfunction "O3_14") (pintype "open_collector"))
      (node (ref "TP7") (pin "TP") (pinfunction "PP_TP") (pintype "input"))
    )
    (net (code "13") (name "Net-(1K-KL)") (class "Default")
      (node (ref "1") (pin "8") (pinfunction "KL_8") (pintype "passive"))
      (node (ref "Q11") (pin "3") (pinfunction "D_3") (pintype "passive"))
      (node (ref "TP8") (pin "TP") (pinfunction "PP_TP") (pintype "input"))
    )
    (net (code "14") (name "Net-(1L-KL)") (class "Default")
      (node (ref "1") (pin "9") (pinfunction "KL_9") (pintype "passive"))
      (node (ref "D10") (pin "1") (pinfunction "+_1") (pintype "passive"))
      (node (ref "TP9") (pin "TP") (pinfunction "PP_TP") (pintype "input"))
      (node (ref "X1") (pin "17") (pinfunction "17_17") (pintype "passive"))
    )
    (net (code "15") (name "Net-(2B-KL)") (class "Default")
      (node (ref "2") (pin "10") (pinfunction "KL_10") (pintype "passive"))
      (node (ref "TP25") (pin "TP") (pinfunction "PP_TP") (pintype "input"))
      (node (ref "X1") (pin "15") (pinfunction "15_15") (pintype "passive"))
    )
    (net (code "16") (name "Net-(2C-KL)") (class "Default")
      (node (ref "2") (pin "11") (pinfunction "KL_11") (pintype "passive"))
      (node (ref "R23") (pin "1") (pinfunction "1_1") (pintype "passive"))
      (node (ref "R3") (pin "1") (pinfunction "1_1") (pintype "passive"))
      (node (ref "TP26") (pin "TP") (pinfunction "PP_TP") (pintype "input"))
    )
    (net (code "17") (name "Net-(2D-KL)") (class "Default")
      (node (ref "2") (pin "12") (pinfunction "KL_12") (pintype "passive"))
      (node (ref "R35") (pin "1") (pinfunction "1_1") (pintype "passive"))
      (node (ref "TP13") (pin "TP") (pinfunction "PP_TP") (pintype "input"))
    )
    (net (code "18") (name "Net-(2E-KL)") (class "Default")
      (node (ref "2") (pin "2") (pinfunction "KL_2") (pintype "passive"))
      (node (ref "D13") (pin "2") (pinfunction "-_2") (pintype "passive"))
      (node (ref "LED1") (pin "K") (pinfunction "C_K") (pintype "passive"))
      (node (ref "TP16") (pin "TP") (pinfunction "PP_TP") (pintype "input"))
      (node (ref "X1") (pin "12") (pinfunction "12_12") (pintype "passive"))
    )
    (net (code "19") (name "Net-(2F-KL)") (class "Default")
      (node (ref "2") (pin "3") (pinfunction "KL_3") (pintype "passive"))
      (node (ref "D12") (pin "2") (pinfunction "-_2") (pintype "passive"))
      (node (ref "LED2") (pin "K") (pinfunction "C_K") (pintype "passive"))
      (node (ref "TP17") (pin "TP") (pinfunction "PP_TP") (pintype "input"))
      (node (ref "X1") (pin "11") (pinfunction "11_11") (pintype "passive"))
    )
    (net (code "20") (name "Net-(2G-KL)") (class "Default")
      (node (ref "2") (pin "4") (pinfunction "KL_4") (pintype "passive"))
      (node (ref "D2") (pin "2") (pinfunction "-_2") (pintype "passive"))
      (node (ref "LED3") (pin "K") (pinfunction "C_K") (pintype "passive"))
      (node (ref "TP18") (pin "TP") (pinfunction "PP_TP") (pintype "input"))
      (node (ref "X1") (pin "10") (pinfunction "10_10") (pintype "passive"))
    )
    (net (code "21") (name "Net-(2H-KL)") (class "Default")
      (node (ref "2") (pin "5") (pinfunction "KL_5") (pintype "passive"))
      (node (ref "D1") (pin "2") (pinfunction "-_2") (pintype "passive"))
      (node (ref "LED4") (pin "K") (pinfunction "C_K") (pintype "passive"))
      (node (ref "TP19") (pin "TP") (pinfunction "PP_TP") (pintype "input"))
      (node (ref "X1") (pin "9") (pinfunction "9_9") (pintype "passive"))
    )
    (net (code "22") (name "Net-(2I-KL)") (class "Default")
      (node (ref "2") (pin "6") (pinfunction "KL_6") (pintype "passive"))
      (node (ref "TP21") (pin "TP") (pinfunction "PP_TP") (pintype "input"))
      (node (ref "U$2") (pin "2") (pinfunction "2_2") (pintype "passive"))
    )
    (net (code "23") (name "Net-(2J-KL)") (class "Default")
      (node (ref "2") (pin "7") (pinfunction "KL_7") (pintype "passive"))
      (node (ref "LED6") (pin "A") (pinfunction "A_A") (pintype "passive"))
      (node (ref "TP22") (pin "TP") (pinfunction "PP_TP") (pintype "input"))
      (node (ref "X1") (pin "8") (pinfunction "8_8") (pintype "passive"))
    )
    (net (code "24") (name "Net-(2K-KL)") (class "Default")
      (node (ref "2") (pin "8") (pinfunction "KL_8") (pintype "passive"))
      (node (ref "D14") (pin "2") (pinfunction "-_2") (pintype "passive"))
      (node (ref "LED7") (pin "K") (pinfunction "C_K") (pintype "passive"))
      (node (ref "TP23") (pin "TP") (pinfunction "PP_TP") (pintype "input"))
      (node (ref "X1") (pin "14") (pinfunction "14_14") (pintype "passive"))
    )
    (net (code "25") (name "Net-(2L-KL)") (class "Default")
      (node (ref "2") (pin "9") (pinfunction "KL_9") (pintype "passive"))
      (node (ref "D12") (pin "1") (pinfunction "+_1") (pintype "passive"))
      (node (ref "D2") (pin "1") (pinfunction "+_1") (pintype "passive"))
      (node (ref "JP2") (pin "1") (pinfunction "1_1") (pintype "passive"))
      (node (ref "JP4") (pin "2") (pinfunction "2_2") (pintype "passive"))
      (node (ref "TP24") (pin "TP") (pinfunction "PP_TP") (pintype "input"))
    )
    (net (code "26") (name "Net-(C2-Pad1)") (class "Default")
      (node (ref "C2") (pin "1") (pinfunction "1_1") (pintype "passive"))
      (node (ref "R10") (pin "1") (pinfunction "1_1") (pintype "passive"))
      (node (ref "R12") (pin "2") (pinfunction "2_2") (pintype "passive"))
    )
    (net (code "27") (name "Net-(C11-Pad1)") (class "Default")
      (node (ref "C11") (pin "1") (pinfunction "1_1") (pintype "passive"))
      (node (ref "R42") (pin "1") (pinfunction "1_1") (pintype "passive"))
      (node (ref "R43") (pin "1") (pinfunction "1_1") (pintype "passive"))
    )
    (net (code "28") (name "Net-(D1-+)") (class "Default")
      (node (ref "D1") (pin "1") (pinfunction "+_1") (pintype "passive"))
      (node (ref "R27") (pin "1") (pinfunction "1_1") (pintype "passive"))
    )
    (net (code "29") (name "Net-(D3-+)") (class "Default")
      (node (ref "D3") (pin "1") (pinfunction "+_1") (pintype "passive"))
      (node (ref "R33") (pin "1") (pinfunction "1_1") (pintype "passive"))
    )
    (net (code "30") (name "Net-(D3--)") (class "Default")
      (node (ref "C1") (pin "2") (pinfunction "2_2") (pintype "passive"))
      (node (ref "D3") (pin "2") (pinfunction "-_2") (pintype "passive"))
      (node (ref "IC5") (pin "2") (pinfunction "TR_2") (pintype "input"))
      (node (ref "IC5") (pin "6") (pinfunction "THR_6") (pintype "input"))
      (node (ref "R24") (pin "1") (pinfunction "1_1") (pintype "passive"))
      (node (ref "U$3") (pin "6") (pinfunction "D2_6") (pintype "passive"))
    )
    (net (code "31") (name "Net-(D8-+)") (class "Default")
      (node (ref "D8") (pin "1") (pinfunction "+_1") (pintype "passive"))
      (node (ref "R17") (pin "1") (pinfunction "1_1") (pintype "passive"))
    )
    (net (code "32") (name "Net-(D8--)") (class "Default")
      (node (ref "D8") (pin "2") (pinfunction "-_2") (pintype "passive"))
      (node (ref "IC7") (pin "2") (pinfunction "OUT_2") (pintype "open_collector"))
      (node (ref "Q10") (pin "1") (pinfunction "G_1") (pintype "passive"))
      (node (ref "R22") (pin "2") (pinfunction "2_2") (pintype "passive"))
      (node (ref "U$2") (pin "1") (pinfunction "1_1") (pintype "passive"))
    )
    (net (code "33") (name "Net-(D13-+)") (class "Default")
      (node (ref "D13") (pin "1") (pinfunction "+_1") (pintype "passive"))
      (node (ref "JP2") (pin "2") (pinfunction "2_2") (pintype "passive"))
    )
    (net (code "34") (name "Net-(D14-+)") (class "Default")
      (node (ref "D14") (pin "1") (pinfunction "+_1") (pintype "passive"))
      (node (ref "JP4") (pin "1") (pinfunction "1_1") (pintype "passive"))
    )
    (net (code "35") (name "Net-(D15--)") (class "Default")
      (node (ref "D15") (pin "2") (pinfunction "-_2") (pintype "passive"))
      (node (ref "Q1") (pin "2") (pinfunction "C_2") (pintype "passive"))
      (node (ref "START") (pin "TP") (pinfunction "PP_TP") (pintype "input"))
      (node (ref "X1") (pin "5") (pinfunction "5_5") (pintype "passive"))
    )
    (net (code "36") (name "Net-(IC3A-A)") (class "Default")
      (node (ref "IC3") (pin "10") (pinfunction "A_10") (pintype "input"))
      (node (ref "R31") (pin "1") (pinfunction "1_1") (pintype "passive"))
      (node (ref "U$3") (pin "1") (pinfunction "D1_1") (pintype "passive"))
      (node (ref "X1") (pin "4") (pinfunction "4_4") (pintype "passive"))
      (node (ref "X3") (pin "2") (pinfunction "S_2") (pintype "passive"))
    )
    (net (code "37") (name "Net-(IC3A-B)") (class "Default")
      (node (ref "IC3") (pin "13") (pinfunction "B_13") (pintype "input"))
      (node (ref "R30") (pin "1") (pinfunction "1_1") (pintype "passive"))
      (node (ref "U$3") (pin "4") (pinfunction "D4_4") (pintype "passive"))
      (node (ref "X1") (pin "3") (pinfunction "3_3") (pintype "passive"))
      (node (ref "X3") (pin "3") (pinfunction "S_3") (pintype "passive"))
    )
    (net (code "38") (name "Net-(IC3A-C)") (class "Default")
      (node (ref "IC3") (pin "12") (pinfunction "C_12") (pintype "input"))
      (node (ref "R29") (pin "1") (pinfunction "1_1") (pintype "passive"))
      (node (ref "U$3") (pin "3") (pinfunction "D3_3") (pintype "passive"))
      (node (ref "X1") (pin "2") (pinfunction "2_2") (pintype "passive"))
      (node (ref "X3") (pin "4") (pinfunction "S_4") (pintype "passive"))
    )
    (net (code "39") (name "Net-(IC3A-Q0)") (class "Default")
      (node (ref "IC3") (pin "3") (pinfunction "Q0_3") (pintype "output"))
      (node (ref "IC6") (pin "1") (pinfunction "I1_1") (pintype "input"))
      (node (ref "IC6") (pin "2") (pinfunction "I2_2") (pintype "input"))
      (node (ref "Q11") (pin "1") (pinfunction "G_1") (pintype "passive"))
    )
    (net (code "40") (name "Net-(IC3A-Q1)") (class "Default")
      (node (ref "IC3") (pin "14") (pinfunction "Q1_14") (pintype "output"))
      (node (ref "IC6") (pin "6") (pinfunction "I6_6") (pintype "input"))
    )
    (net (code "41") (name "Net-(IC3A-Q2)") (class "Default")
      (node (ref "IC3") (pin "2") (pinfunction "Q2_2") (pintype "output"))
      (node (ref "IC6") (pin "7") (pinfunction "I7_7") (pintype "input"))
    )
    (net (code "42") (name "Net-(IC3A-Q3)") (class "Default")
      (node (ref "IC3") (pin "15") (pinfunction "Q3_15") (pintype "output"))
      (node (ref "IC6") (pin "5") (pinfunction "I5_5") (pintype "input"))
    )
    (net (code "43") (name "Net-(IC3A-Q4)") (class "Default")
      (node (ref "IC3") (pin "1") (pinfunction "Q4_1") (pintype "output"))
      (node (ref "IC6") (pin "4") (pinfunction "I4_4") (pintype "input"))
    )
    (net (code "44") (name "Net-(IC3A-Q5)") (class "Default")
      (node (ref "IC3") (pin "6") (pinfunction "Q5_6") (pintype "output"))
      (node (ref "IC6") (pin "3") (pinfunction "I3_3") (pintype "input"))
    )
    (net (code "45") (name "Net-(IC4-ADJ)") (class "Default")
      (node (ref "IC4") (pin "1") (pinfunction "ADJ_1") (pintype "input"))
      (node (ref "R18") (pin "1") (pinfunction "1_1") (pintype "passive"))
      (node (ref "R5") (pin "2") (pinfunction "2_2") (pintype "passive"))
      (node (ref "X1") (pin "7") (pinfunction "7_7") (pintype "passive"))
    )
    (net (code "46") (name "Net-(IC4-VI)") (class "Default")
      (node (ref "IC4") (pin "3") (pinfunction "VI_3") (pintype "input"))
      (node (ref "Q2") (pin "2") (pinfunction "C_2") (pintype "passive"))
    )
    (net (code "47") (name "Net-(IC4-VO)") (class "Default")
      (node (ref "IC4") (pin "2") (pinfunction "VO_2") (pintype "passive"))
      (node (ref "R18") (pin "2") (pinfunction "2_2") (pintype "passive"))
    )
    (net (code "48") (name "Net-(IC5-Q)") (class "Default")
      (node (ref "IC5") (pin "3") (pinfunction "Q_3") (pintype "output"))
      (node (ref "IC8") (pin "12") (pinfunction "A_12") (pintype "input"))
    )
    (net (code "49") (name "Net-(IC6-O1)") (class "Default")
      (node (ref "IC6") (pin "16") (pinfunction "O1_16") (pintype "open_collector"))
      (node (ref "Q9") (pin "2") (pinfunction "C_2") (pintype "passive"))
      (node (ref "R3") (pin "2") (pinfunction "2_2") (pintype "passive"))
      (node (ref "X1") (pin "21") (pinfunction "21_21") (pintype "passive"))
    )
    (net (code "50") (name "Net-(IC6-O2)") (class "Default")
      (node (ref "IC6") (pin "15") (pinfunction "O2_15") (pintype "open_collector"))
      (node (ref "R13") (pin "1") (pinfunction "1_1") (pintype "passive"))
    )
    (net (code "51") (name "Net-(IC7A-+IN)") (class "Default")
      (node (ref "IC7") (pin "5") (pinfunction "+IN_5") (pintype "input"))
      (node (ref "R15") (pin "1") (pinfunction "1_1") (pintype "passive"))
      (node (ref "R16") (pin "2") (pinfunction "2_2") (pintype "passive"))
      (node (ref "R17") (pin "2") (pinfunction "2_2") (pintype "passive"))
    )
    (net (code "52") (name "Net-(IC7A--IN)") (class "Default")
      (node (ref "C3") (pin "1") (pinfunction "1_1") (pintype "passive"))
      (node (ref "IC7") (pin "4") (pinfunction "-IN_4") (pintype "input"))
      (node (ref "R12") (pin "1") (pinfunction "1_1") (pintype "passive"))
    )
    (net (code "53") (name "Net-(IC7B-+IN)") (class "Default")
      (node (ref "IC7") (pin "7") (pinfunction "+IN_7") (pintype "input"))
      (node (ref "R25") (pin "1") (pinfunction "1_1") (pintype "passive"))
      (node (ref "R6") (pin "1") (pinfunction "1_1") (pintype "passive"))
    )
    (net (code "54") (name "Net-(IC7B--IN)") (class "Default")
      (node (ref "IC7") (pin "6") (pinfunction "-IN_6") (pintype "input"))
      (node (ref "IC7") (pin "8") (pinfunction "-IN_8") (pintype "input"))
      (node (ref "R5") (pin "1") (pinfunction "1_1") (pintype "passive"))
    )
    (net (code "55") (name "Net-(IC7B-OUT)") (class "Default")
      (node (ref "IC7") (pin "1") (pinfunction "OUT_1") (pintype "open_collector"))
      (node (ref "R10") (pin "2") (pinfunction "2_2") (pintype "passive"))
      (node (ref "R19") (pin "2") (pinfunction "2_2") (pintype "passive"))
    )
    (net (code "56") (name "Net-(IC7C-+IN)") (class "Default")
      (node (ref "C5") (pin "1") (pinfunction "1_1") (pintype "passive"))
      (node (ref "IC7") (pin "9") (pinfunction "+IN_9") (pintype "input"))
      (node (ref "R25") (pin "2") (pinfunction "2_2") (pintype "passive"))
      (node (ref "R8") (pin "2") (pinfunction "2_2") (pintype "passive"))
    )
    (net (code "57") (name "Net-(IC7C-OUT)") (class "Default")
      (node (ref "C9") (pin "2") (pinfunction "2_2") (pintype "passive"))
      (node (ref "IC7") (pin "14") (pinfunction "OUT_14") (pintype "open_collector"))
      (node (ref "R9") (pin "2") (pinfunction "2_2") (pintype "passive"))
    )
    (net (code "58") (name "Net-(IC8B-B)") (class "Default")
      (node (ref "IC8") (pin "11") (pinfunction "B_11") (pintype "input"))
      (node (ref "IC8") (pin "9") (pinfunction "~{Q}_9") (pintype "output"))
      (node (ref "R35") (pin "2") (pinfunction "2_2") (pintype "passive"))
    )
    (net (code "59") (name "Net-(IC8B-T2)") (class "Default")
      (node (ref "C10") (pin "1") (pinfunction "1_1") (pintype "passive"))
      (node (ref "IC8") (pin "14") (pinfunction "T2_14") (pintype "input"))
      (node (ref "R34") (pin "1") (pinfunction "1_1") (pintype "passive"))
    )
    (net (code "60") (name "Net-(IC10A-+IN)") (class "Default")
      (node (ref "C8") (pin "1") (pinfunction "1_1") (pintype "passive"))
      (node (ref "IC10") (pin "3") (pinfunction "+IN_3") (pintype "input"))
      (node (ref "R1") (pin "1") (pinfunction "1_1") (pintype "passive"))
    )
    (net (code "61") (name "Net-(IC10A--IN)") (class "Default")
      (node (ref "IC10") (pin "2") (pinfunction "-IN_2") (pintype "input"))
      (node (ref "R2") (pin "2") (pinfunction "2_2") (pintype "passive"))
    )
    (net (code "62") (name "Net-(IC10A-OUT)") (class "Default")
      (node (ref "IC10") (pin "1") (pinfunction "OUT_1") (pintype "output"))
      (node (ref "R42") (pin "2") (pinfunction "2_2") (pintype "passive"))
    )
    (net (code "63") (name "Net-(IC10B-+IN)") (class "Default")
      (node (ref "IC10") (pin "5") (pinfunction "+IN_5") (pintype "input"))
      (node (ref "R43") (pin "2") (pinfunction "2_2") (pintype "passive"))
      (node (ref "R44") (pin "2") (pinfunction "2_2") (pintype "passive"))
    )
    (net (code "64") (name "Net-(IC10B--IN)") (class "Default")
      (node (ref "IC10") (pin "6") (pinfunction "-IN_6") (pintype "input"))
      (node (ref "R45") (pin "1") (pinfunction "1_1") (pintype "passive"))
      (node (ref "R46") (pin "2") (pinfunction "2_2") (pintype "passive"))
    )
    (net (code "65") (name "Net-(IC10B-OUT)") (class "Default")
      (node (ref "IC10") (pin "7") (pinfunction "OUT_7") (pintype "output"))
      (node (ref "R32") (pin "1") (pinfunction "1_1") (pintype "passive"))
      (node (ref "R44") (pin "1") (pinfunction "1_1") (pintype "passive"))
    )
    (net (code "66") (name "Net-(JP1-Pad2)") (class "Default")
      (node (ref "JP1") (pin "2") (pinfunction "2_2") (pintype "passive"))
      (node (ref "R36") (pin "2") (pinfunction "2_2") (pintype "passive"))
      (node (ref "R37") (pin "2") (pinfunction "2_2") (pintype "passive"))
    )
    (net (code "67") (name "Net-(JP3-Pad1)") (class "Default")
      (node (ref "JP3") (pin "1") (pinfunction "1_1") (pintype "passive"))
      (node (ref "R23") (pin "2") (pinfunction "2_2") (pintype "passive"))
    )
    (net (code "68") (name "Net-(LED1-PadA)") (class "Default")
      (node (ref "LED1") (pin "A") (pinfunction "A_A") (pintype "passive"))
      (node (ref "LED2") (pin "A") (pinfunction "A_A") (pintype "passive"))
      (node (ref "LED3") (pin "A") (pinfunction "A_A") (pintype "passive"))
      (node (ref "LED4") (pin "A") (pinfunction "A_A") (pintype "passive"))
      (node (ref "LED7") (pin "A") (pinfunction "A_A") (pintype "passive"))
      (node (ref "R11") (pin "1") (pinfunction "1_1") (pintype "passive"))
    )
    (net (code "69") (name "Net-(LED6-C)") (class "Default")
      (node (ref "LED6") (pin "K") (pinfunction "C_K") (pintype "passive"))
      (node (ref "R4") (pin "1") (pinfunction "1_1") (pintype "passive"))
    )
    (net (code "70") (name "Net-(Q1-B)") (class "Default")
      (node (ref "Q1") (pin "1") (pinfunction "B_1") (pintype "passive"))
      (node (ref "R13") (pin "2") (pinfunction "2_2") (pintype "passive"))
    )
    (net (code "71") (name "Net-(Q2-B)") (class "Default")
      (node (ref "Q2") (pin "1") (pinfunction "B_1") (pintype "passive"))
      (node (ref "R9") (pin "1") (pinfunction "1_1") (pintype "passive"))
    )
    (net (code "72") (name "Net-(Q7-B)") (class "Default")
      (node (ref "Q7") (pin "1") (pinfunction "B_1") (pintype "passive"))
      (node (ref "Q7") (pin "2") (pinfunction "C_2") (pintype "passive"))
      (node (ref "Q8") (pin "1") (pinfunction "B_1") (pintype "passive"))
      (node (ref "R38") (pin "1") (pinfunction "1_1") (pintype "passive"))
      (node (ref "X2") (pin "2") (pinfunction "S_2") (pintype "passive"))
    )
    (net (code "73") (name "Net-(Q7-E)") (class "Default")
      (node (ref "Q7") (pin "3") (pinfunction "E_3") (pintype "passive"))
      (node (ref "R20") (pin "2") (pinfunction "2_2") (pintype "passive"))
    )
    (net (code "74") (name "Net-(Q8-E)") (class "Default")
      (node (ref "Q8") (pin "3") (pinfunction "E_3") (pintype "passive"))
      (node (ref "R21") (pin "2") (pinfunction "2_2") (pintype "passive"))
    )
    (net (code "75") (name "Net-(Q9-B)") (class "Default")
      (node (ref "Q9") (pin "1") (pinfunction "B_1") (pintype "passive"))
      (node (ref "R32") (pin "2") (pinfunction "2_2") (pintype "passive"))
    )
    (net (code "76") (name "Net-(Q10-D)") (class "Default")
      (node (ref "Q10") (pin "3") (pinfunction "D_3") (pintype "passive"))
      (node (ref "R7") (pin "2") (pinfunction "2_2") (pintype "passive"))
    )
    (net (code "77") (name "Net-(R1-Pad2)") (class "Default")
      (node (ref "R1") (pin "2") (pinfunction "2_2") (pintype "passive"))
      (node (ref "X1") (pin "22") (pinfunction "22_22") (pintype "passive"))
    )
    (net (code "78") (name "Net-(R14-Pad1)") (class "Default")
      (node (ref "R14") (pin "1") (pinfunction "1_1") (pintype "passive"))
      (node (ref "R7") (pin "1") (pinfunction "1_1") (pintype "passive"))
      (node (ref "U$2") (pin "3") (pinfunction "3_3") (pintype "passive"))
    )
    (net (code "79") (name "Net-(R27-Pad2)") (class "Default")
      (node (ref "R27") (pin "2") (pinfunction "2_2") (pintype "passive"))
      (node (ref "R28") (pin "1") (pinfunction "1_1") (pintype "passive"))
    )
    (net (code "80") (name "Net-(R33-Pad2)") (class "Default")
      (node (ref "R33") (pin "2") (pinfunction "2_2") (pintype "passive"))
      (node (ref "X1") (pin "16") (pinfunction "16_16") (pintype "passive"))
    )
    (net (code "81") (name "VCC") (class "Default")
      (node (ref "6V") (pin "TP") (pinfunction "PP_TP") (pintype "input"))
      (node (ref "C4") (pin "1") (pinfunction "1_1") (pintype "passive"))
      (node (ref "IC1") (pin "OUT") (pinfunction "OUT_OUT") (pintype "passive"))
      (node (ref "IC10") (pin "8") (pinfunction "V+_8") (pintype "power_in"))
      (node (ref "IC2") (pin "1") (pinfunction "OUT_1") (pintype "passive"))
      (node (ref "IC7") (pin "3") (pinfunction "V+_3") (pintype "power_in"))
      (node (ref "R11") (pin "2") (pinfunction "2_2") (pintype "passive"))
      (node (ref "R15") (pin "2") (pinfunction "2_2") (pintype "passive"))
      (node (ref "R19") (pin "1") (pinfunction "1_1") (pintype "passive"))
      (node (ref "R45") (pin "2") (pinfunction "2_2") (pintype "passive"))
      (node (ref "R6") (pin "2") (pinfunction "2_2") (pintype "passive"))
    )
    (net (code "82") (name "unconnected-(IC3A-Q6-Pad7)") (class "Default")
      (node (ref "IC3") (pin "7") (pinfunction "Q6_7") (pintype "output"))
    )
    (net (code "83") (name "unconnected-(IC3A-Q7-Pad4)") (class "Default")
      (node (ref "IC3") (pin "4") (pinfunction "Q7_4") (pintype "output"))
    )
    (net (code "84") (name "unconnected-(IC3A-Q8-Pad9)") (class "Default")
      (node (ref "IC3") (pin "9") (pinfunction "Q8_9") (pintype "output"))
    )
    (net (code "85") (name "unconnected-(IC3A-Q9-Pad5)") (class "Default")
      (node (ref "IC3") (pin "5") (pinfunction "Q9_5") (pintype "output"))
    )
    (net (code "86") (name "unconnected-(IC5-CV-Pad5)") (class "Default")
      (node (ref "IC5") (pin "5") (pinfunction "CV_5") (pintype "input"))
    )
    (net (code "87") (name "unconnected-(IC5-DIS-Pad7)") (class "Default")
      (node (ref "IC5") (pin "7") (pinfunction "DIS_7") (pintype "input"))
    )
    (net (code "88") (name "unconnected-(IC7D-OUT-Pad13)") (class "Default")
      (node (ref "IC7") (pin "13") (pinfunction "OUT_13") (pintype "open_collector"))
    )
    (net (code "89") (name "unconnected-(IC8A-Q-Pad6)") (class "Default")
      (node (ref "IC8") (pin "6") (pinfunction "Q_6") (pintype "output"))
    )
    (net (code "90") (name "unconnected-(IC8A-T2-Pad2)") (class "Default")
      (node (ref "IC8") (pin "2") (pinfunction "T2_2") (pintype "input"))
    )
    (net (code "91") (name "unconnected-(IC8A-~{Q}-Pad7)") (class "Default")
      (node (ref "IC8") (pin "7") (pinfunction "~{Q}_7") (pintype "output"))
    )
    (net (code "92") (name "unconnected-(IC8B-Q-Pad10)") (class "Default")
      (node (ref "IC8") (pin "10") (pinfunction "Q_10") (pintype "output"))
    )
    (net (code "93") (name "unconnected-(X1-Pad20)") (class "Default")
      (node (ref "X1") (pin "20") (pinfunction "20_20") (pintype "passive"))
    )
    (net (code "94") (name "unconnected-(X1-Pad24)") (class "Default")
      (node (ref "X1") (pin "24") (pinfunction "24_24") (pintype "passive"))
    )
  )
)
